# tanaBoard.net
KiCad netlist of a schematic drawn in EasyEDA
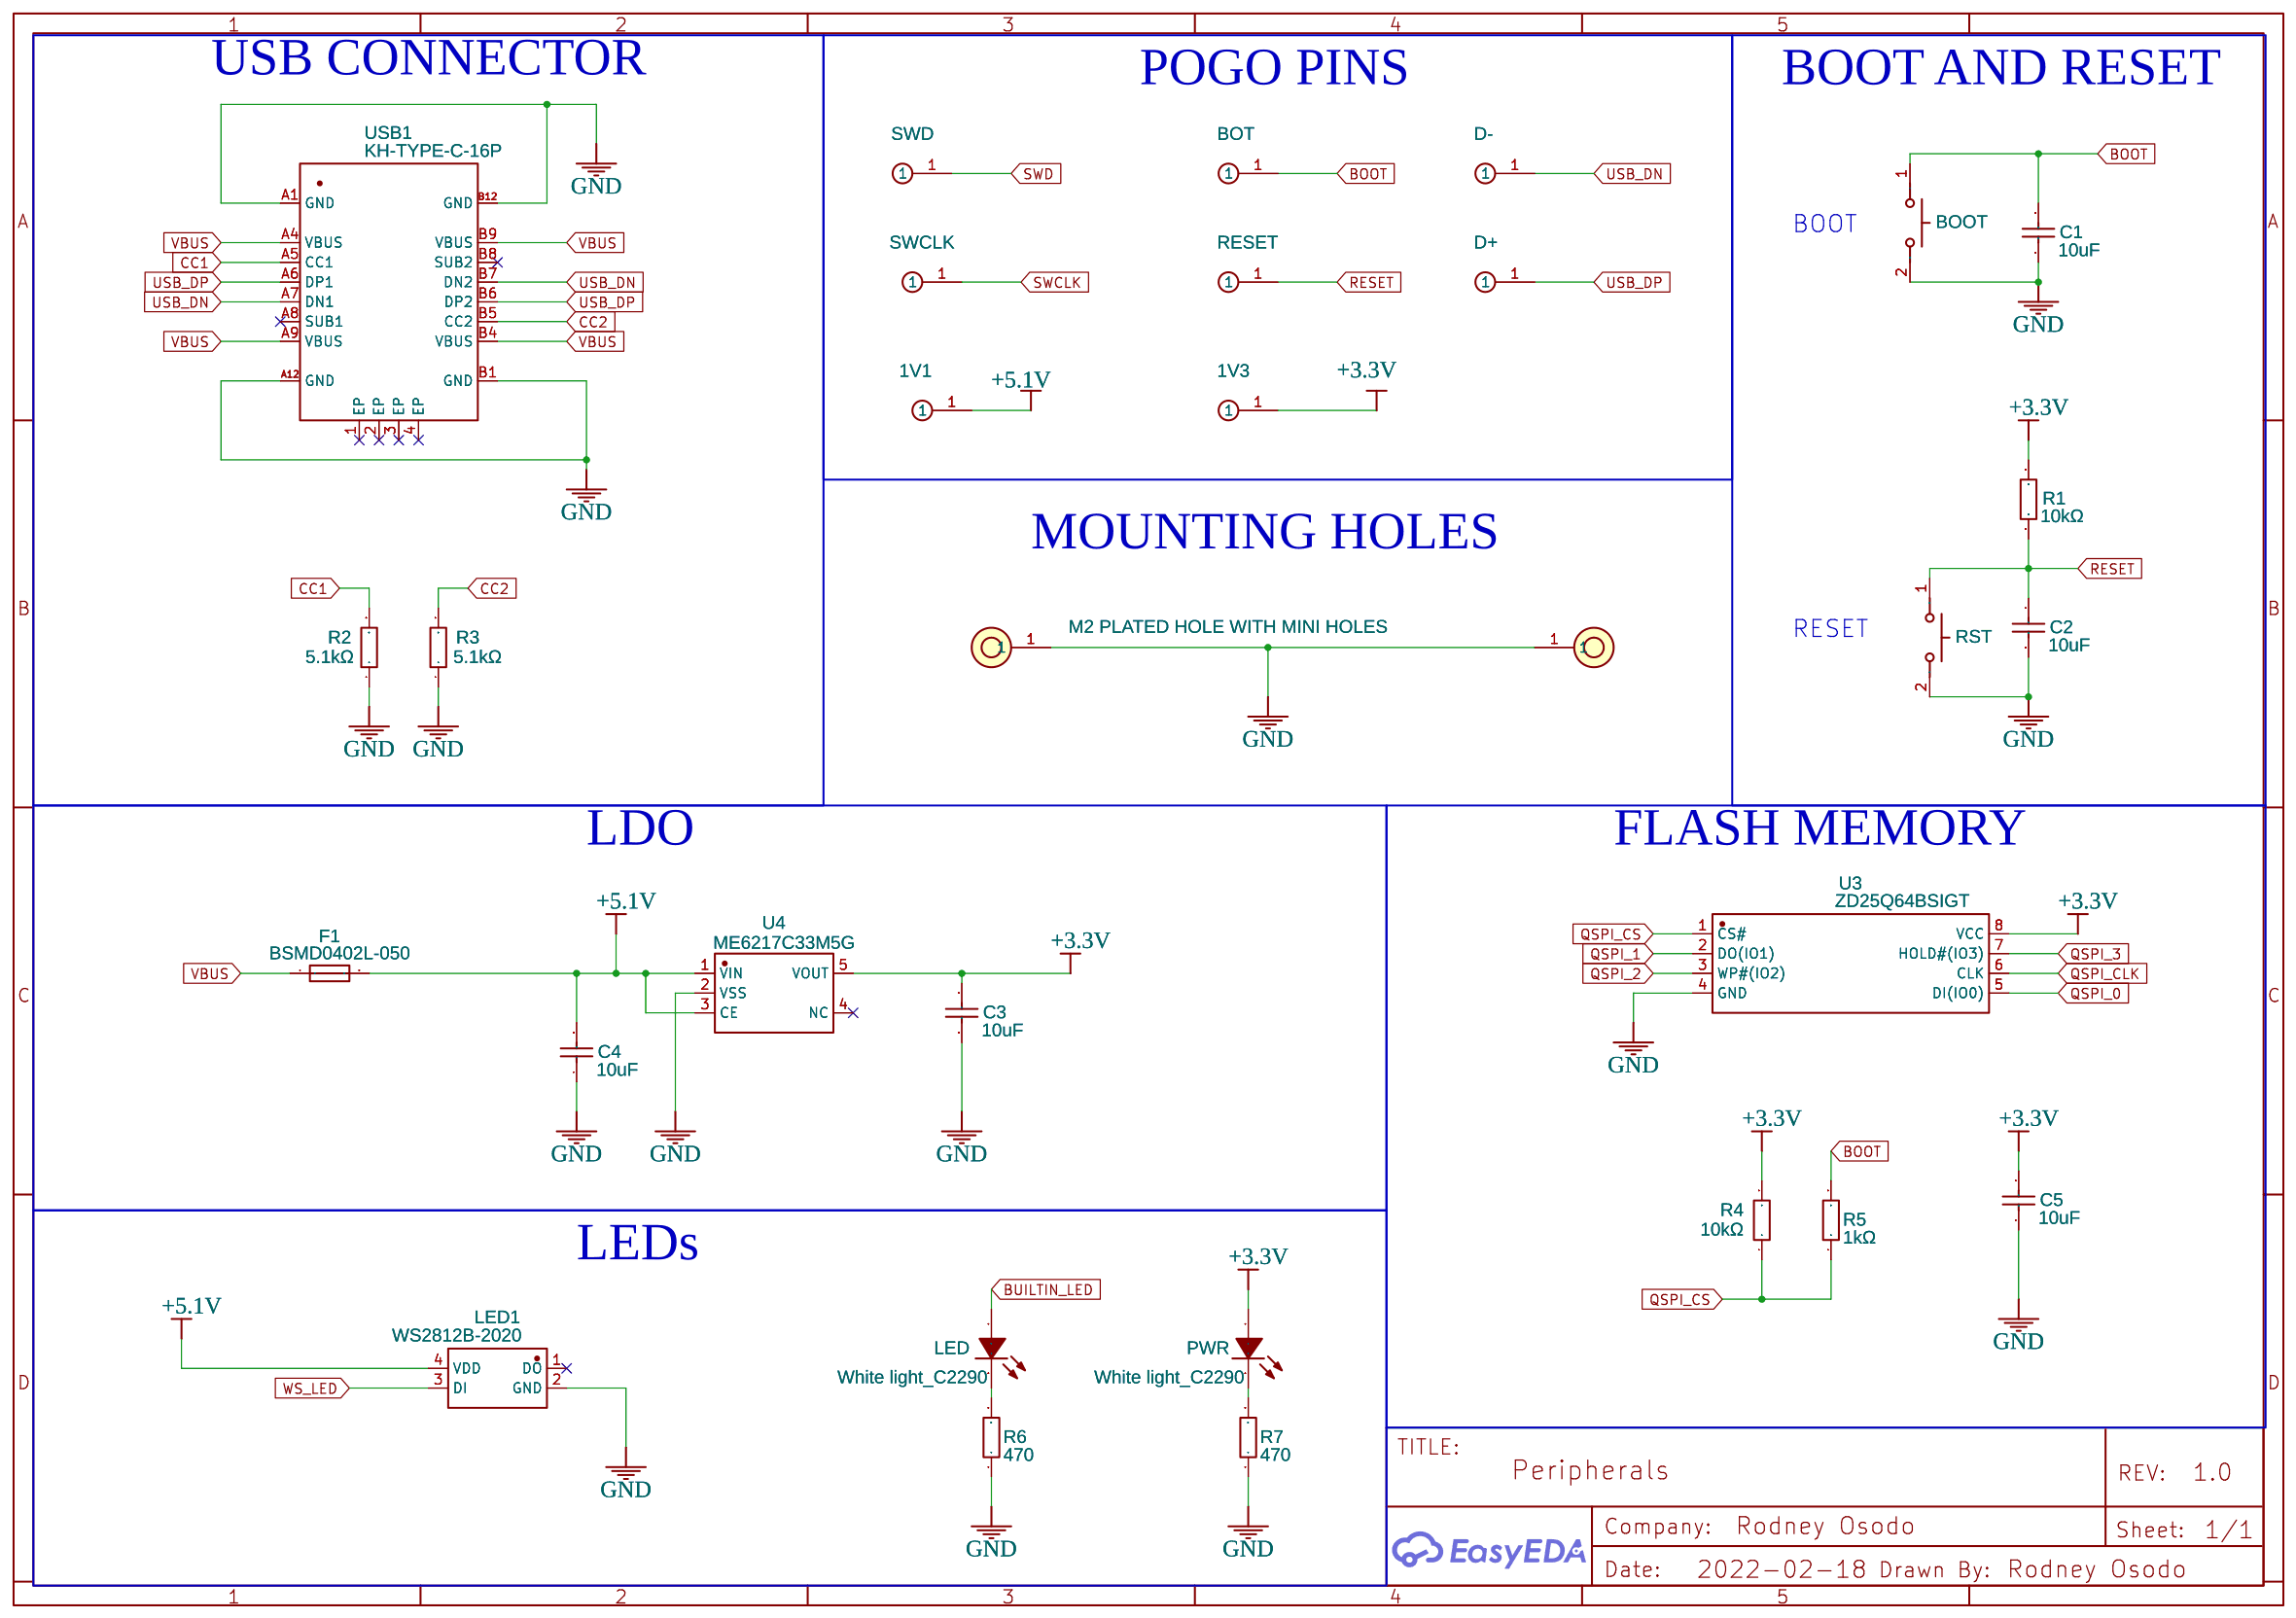
[diagram p0: Peripherals]
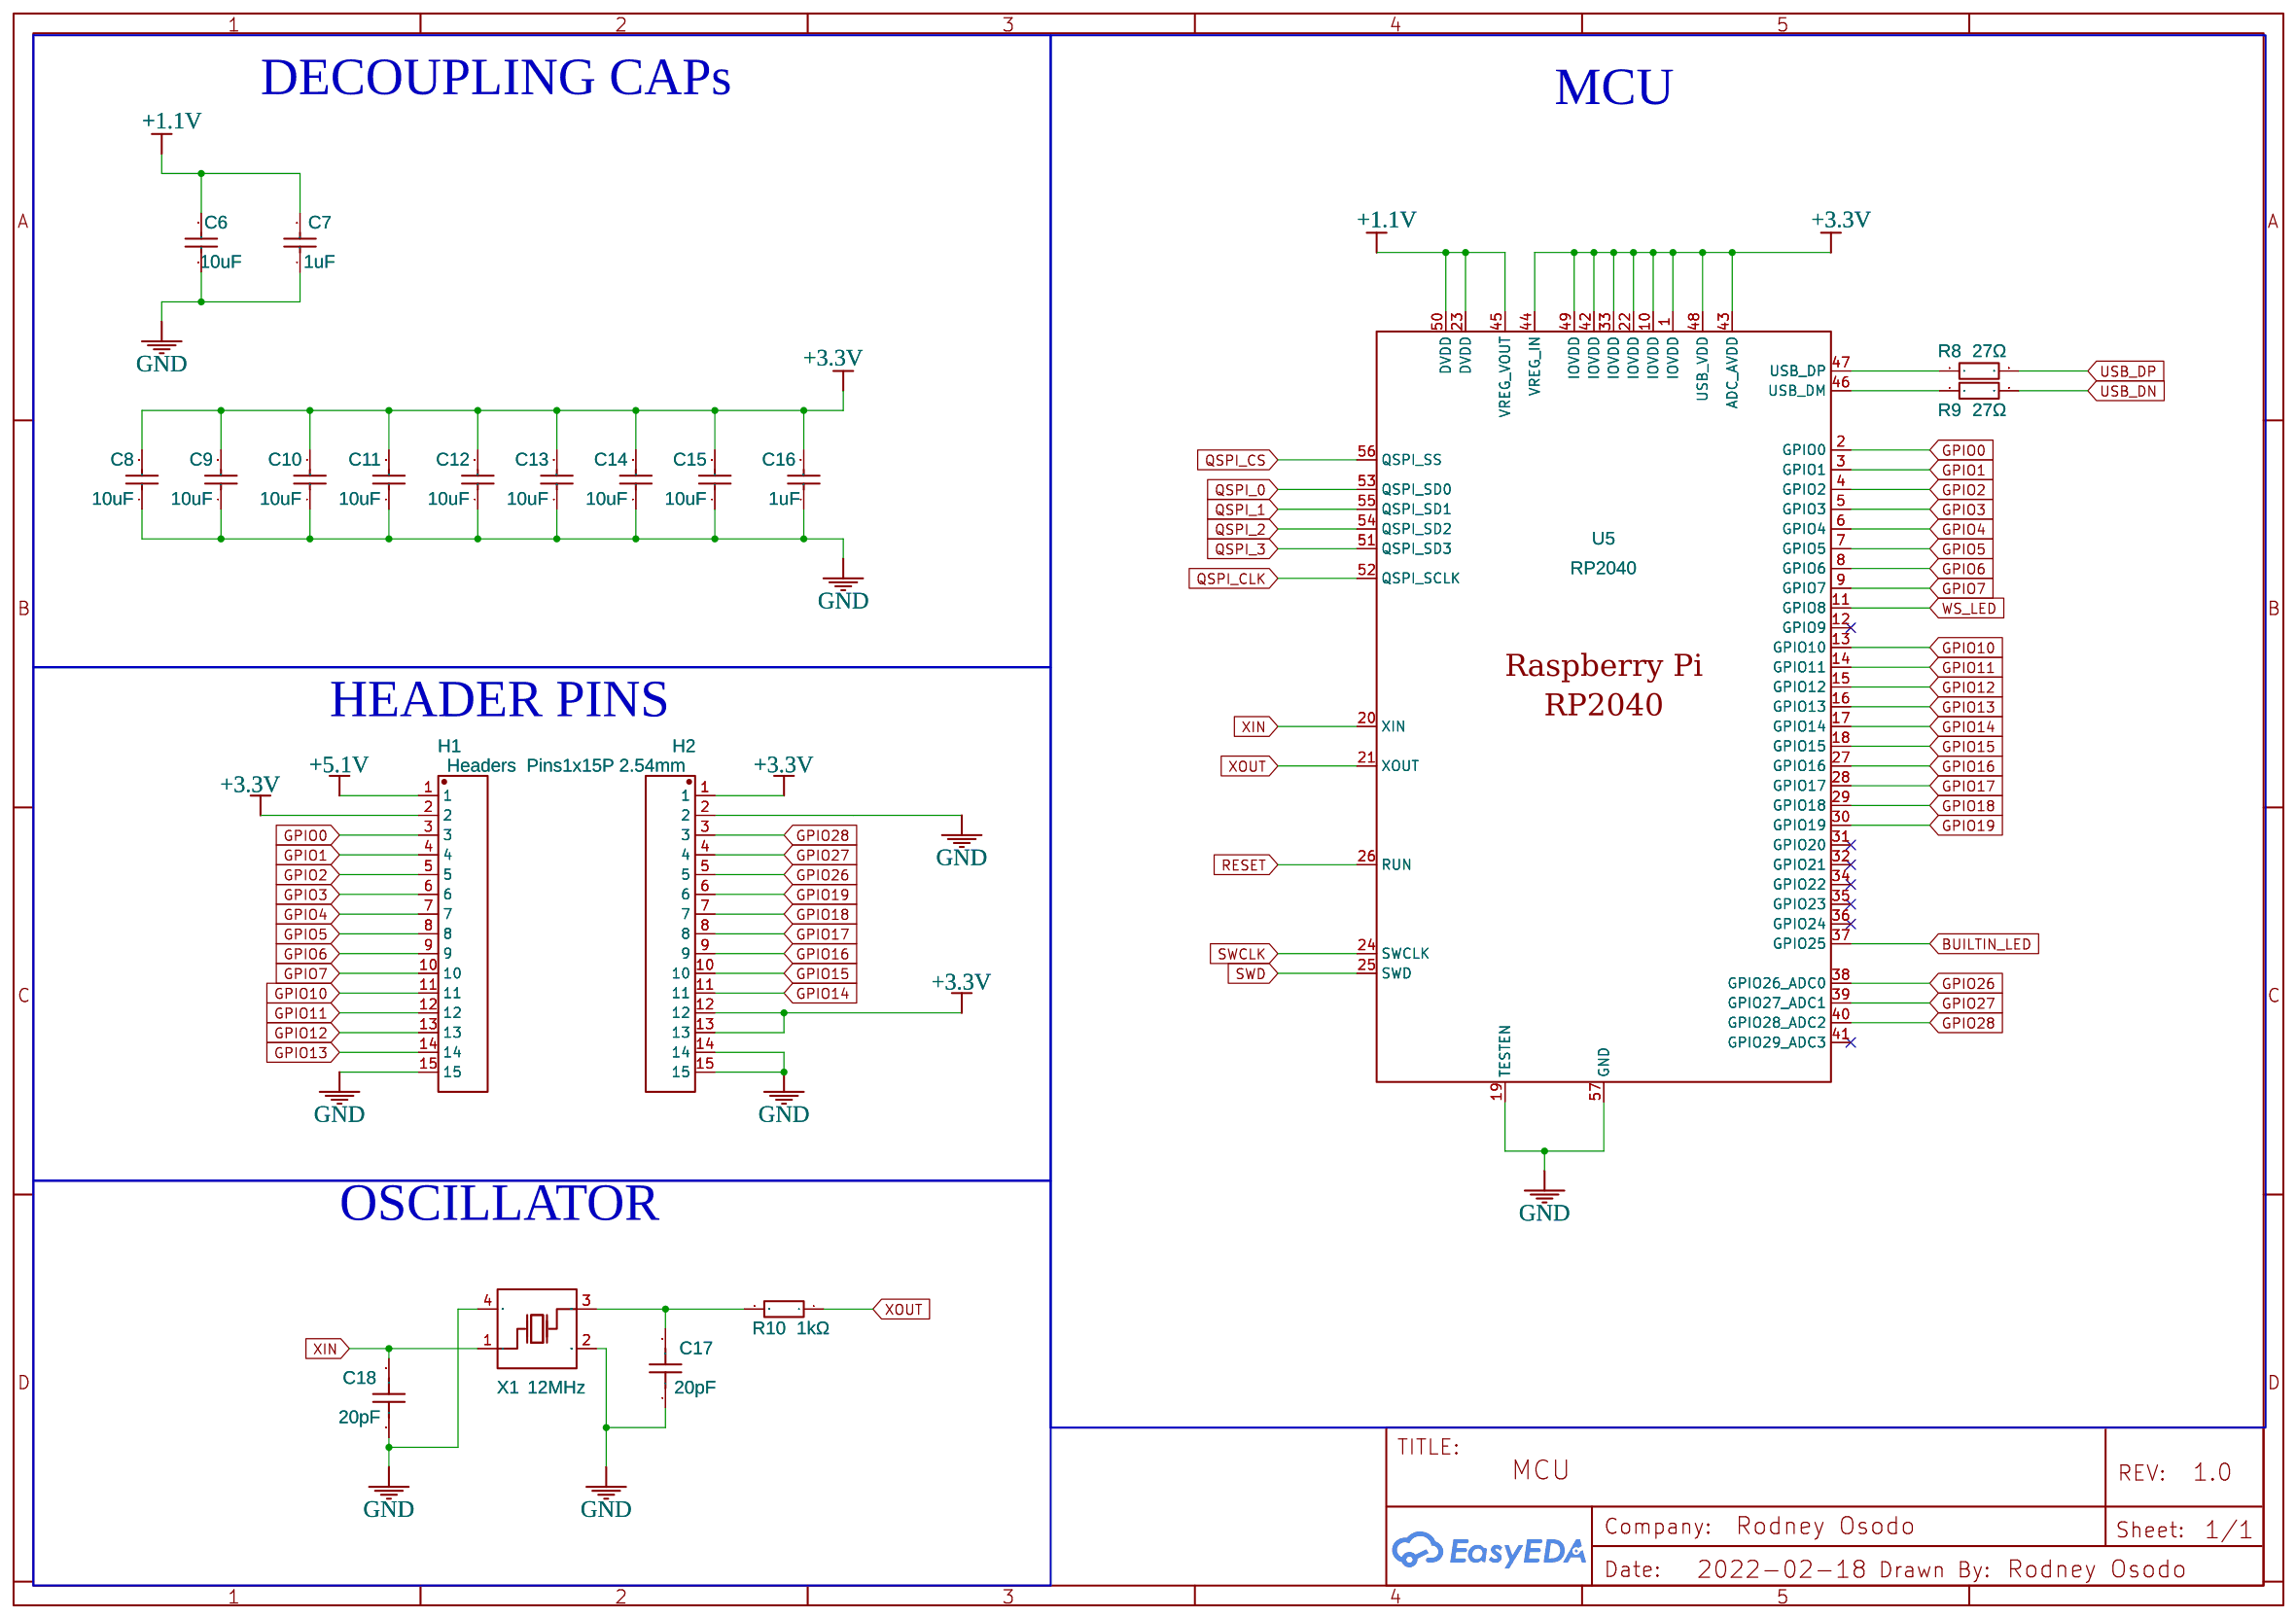
[diagram p1: MCU]

(export (version "E")
  (design (tool "Eeschema 10.0.6"))
  (components
    (comp (ref "1V1") (value "testpoint") (libsource (lib "") (part "testpoint_1")))
    (comp (ref "1V3") (value "testpoint") (libsource (lib "") (part "testpoint_1")))
    (comp (ref "BOOT")
      (value "SKRKAEE020")
      (fields (field (name "BOM_Supplier Part") "C115357"))
      (libsource (lib "") (part "SKRKAEE020"))
    )
    (comp (ref "BOT") (value "testpoint") (libsource (lib "") (part "testpoint")))
    (comp (ref "C1")
      (value "10uF")
      (fields
        (field (name "BOM_Manufacturer Part") "CL05A106MQ5NUNC")
        (field (name "BOM_Supplier Part") "C15525")
      )
      (libsource (lib "") (part "CL05A106MQ5NUNC_1"))
    )
    (comp (ref "C2")
      (value "10uF")
      (fields
        (field (name "BOM_Manufacturer Part") "CL05A106MQ5NUNC")
        (field (name "BOM_Supplier Part") "C15525")
      )
      (libsource (lib "") (part "CL05A106MQ5NUNC_1"))
    )
    (comp (ref "C3")
      (value "10uF")
      (fields
        (field (name "BOM_Manufacturer Part") "CL05A106MQ5NUNC")
        (field (name "BOM_Supplier Part") "C15525")
      )
      (libsource (lib "") (part "CL05A106MQ5NUNC"))
    )
    (comp (ref "C4")
      (value "10uF")
      (fields
        (field (name "BOM_Manufacturer Part") "CL05A106MQ5NUNC")
        (field (name "BOM_Supplier Part") "C15525")
      )
      (libsource (lib "") (part "CL05A106MQ5NUNC"))
    )
    (comp (ref "C5")
      (value "10uF")
      (fields
        (field (name "BOM_Manufacturer Part") "CL05A106MQ5NUNC")
        (field (name "BOM_Supplier Part") "C15525")
      )
      (libsource (lib "") (part "CL05A106MQ5NUNC"))
    )
    (comp (ref "D+") (value "testpoint") (libsource (lib "") (part "testpoint_5")))
    (comp (ref "D-") (value "testpoint") (libsource (lib "") (part "testpoint_6")))
    (comp (ref "F1")
      (value "BSMD0402L-050")
      (fields (field (name "BOM_Supplier Part") "C914087"))
      (libsource (lib "") (part "BSMD0402L-050"))
    )
    (comp (ref "LED")
      (value "White light_C2290")
      (fields
        (field (name "BOM_Manufacturer Part") "0603White light")
        (field (name "BOM_Supplier Part") "C2290")
      )
      (libsource (lib "") (part "0603White light_C2290"))
    )
    (comp (ref "LED1")
      (value "WS2812B-2020")
      (fields (field (name "BOM_Supplier Part") "C965555"))
      (libsource (lib "") (part "WS2812B-2020"))
    )
    (comp (ref "PWR")
      (value "White light_C2290")
      (fields
        (field (name "BOM_Manufacturer Part") "0603White light")
        (field (name "BOM_Supplier Part") "C2290")
      )
      (libsource (lib "") (part "0603White light_C2290_1"))
    )
    (comp (ref "R1")
      (value "10kΩ")
      (fields
        (field (name "BOM_Manufacturer Part") "RC-02W1002FT")
        (field (name "BOM_Supplier Part") "C258091")
      )
      (libsource (lib "") (part "RC-02W1002FT"))
    )
    (comp (ref "R2")
      (value "5.1kΩ")
      (fields
        (field (name "BOM_Manufacturer Part") "RC-02W5101FT")
        (field (name "BOM_Supplier Part") "C294638")
      )
      (libsource (lib "") (part "RC-02W5101FT"))
    )
    (comp (ref "R3")
      (value "5.1kΩ")
      (fields
        (field (name "BOM_Manufacturer Part") "RC-02W5101FT")
        (field (name "BOM_Supplier Part") "C294638")
      )
      (libsource (lib "") (part "RC-02W5101FT"))
    )
    (comp (ref "R4")
      (value "10kΩ")
      (fields
        (field (name "BOM_Manufacturer Part") "RC-02W1002FT")
        (field (name "BOM_Supplier Part") "C258091")
      )
      (libsource (lib "") (part "RC-02W1002FT"))
    )
    (comp (ref "R5")
      (value "1kΩ")
      (fields
        (field (name "BOM_Manufacturer Part") "RC-02W1001FT")
        (field (name "BOM_Supplier Part") "C226166")
      )
      (libsource (lib "") (part "RC-02W1001FT"))
    )
    (comp (ref "R6")
      (value "470")
      (fields
        (field (name "BOM_Manufacturer Part") "RC0402FR-07470RL")
        (field (name "BOM_Supplier Part") "C114877")
      )
      (libsource (lib "") (part "RC0402FR-07470RL"))
    )
    (comp (ref "R7")
      (value "470")
      (fields
        (field (name "BOM_Manufacturer Part") "RC0402FR-07470RL")
        (field (name "BOM_Supplier Part") "C114877")
      )
      (libsource (lib "") (part "RC0402FR-07470RL"))
    )
    (comp (ref "RESET") (value "testpoint") (libsource (lib "") (part "testpoint_3")))
    (comp (ref "RST")
      (value "SKRKAEE020")
      (fields (field (name "BOM_Supplier Part") "C115357"))
      (libsource (lib "") (part "SKRKAEE020_1"))
    )
    (comp (ref "SWCLK") (value "testpoint") (libsource (lib "") (part "testpoint_2")))
    (comp (ref "SWD") (value "testpoint") (libsource (lib "") (part "testpoint_4")))
    (comp (ref "U1")
      (value "M2 PLATED HOLE WITH MINI HOLES")
      (libsource (lib "") (part "M2 PLATED HOLE WITH MINI HOLES_1"))
    )
    (comp (ref "U2")
      (value "M2 PLATED HOLE WITH MINI HOLES")
      (libsource (lib "") (part "M2 PLATED HOLE WITH MINI HOLES"))
    )
    (comp (ref "U3")
      (value "ZD25Q64BSIGT")
      (fields (field (name "BOM_Supplier Part") "C2687407"))
      (libsource (lib "") (part "ZD25Q64BSIGT"))
    )
    (comp (ref "U4")
      (value "ME6217C33M5G")
      (fields (field (name "BOM_Supplier Part") "C427602"))
      (libsource (lib "") (part "ME6217C33M5G"))
    )
    (comp (ref "USB1")
      (value "KH-TYPE-C-16P")
      (fields (field (name "BOM_Supplier Part") "C709357"))
      (libsource (lib "") (part "KH-TYPE-C-16P"))
    )
    (comp (ref "C6")
      (value "10uF")
      (fields
        (field (name "BOM_Manufacturer Part") "CL05A106MQ5NUNC")
        (field (name "BOM_Supplier Part") "C15525")
      )
      (libsource (lib "") (part "CL05A106MQ5NUNC_1"))
    )
    (comp (ref "C7")
      (value "1uF")
      (fields
        (field (name "BOM_Manufacturer Part") "CL05A105KP5NNNC")
        (field (name "BOM_Supplier Part") "C14445")
      )
      (libsource (lib "") (part "CL05A105KP5NNNC"))
    )
    (comp (ref "C8")
      (value "10uF")
      (fields
        (field (name "BOM_Manufacturer Part") "CL05A106MQ5NUNC")
        (field (name "BOM_Supplier Part") "C15525")
      )
      (libsource (lib "") (part "CL05A106MQ5NUNC"))
    )
    (comp (ref "C9")
      (value "10uF")
      (fields
        (field (name "BOM_Manufacturer Part") "CL05A106MQ5NUNC")
        (field (name "BOM_Supplier Part") "C15525")
      )
      (libsource (lib "") (part "CL05A106MQ5NUNC"))
    )
    (comp (ref "C10")
      (value "10uF")
      (fields
        (field (name "BOM_Manufacturer Part") "CL05A106MQ5NUNC")
        (field (name "BOM_Supplier Part") "C15525")
      )
      (libsource (lib "") (part "CL05A106MQ5NUNC"))
    )
    (comp (ref "C11")
      (value "10uF")
      (fields
        (field (name "BOM_Manufacturer Part") "CL05A106MQ5NUNC")
        (field (name "BOM_Supplier Part") "C15525")
      )
      (libsource (lib "") (part "CL05A106MQ5NUNC"))
    )
    (comp (ref "C12")
      (value "10uF")
      (fields
        (field (name "BOM_Manufacturer Part") "CL05A106MQ5NUNC")
        (field (name "BOM_Supplier Part") "C15525")
      )
      (libsource (lib "") (part "CL05A106MQ5NUNC"))
    )
    (comp (ref "C13")
      (value "10uF")
      (fields
        (field (name "BOM_Manufacturer Part") "CL05A106MQ5NUNC")
        (field (name "BOM_Supplier Part") "C15525")
      )
      (libsource (lib "") (part "CL05A106MQ5NUNC"))
    )
    (comp (ref "C14")
      (value "10uF")
      (fields
        (field (name "BOM_Manufacturer Part") "CL05A106MQ5NUNC")
        (field (name "BOM_Supplier Part") "C15525")
      )
      (libsource (lib "") (part "CL05A106MQ5NUNC"))
    )
    (comp (ref "C15")
      (value "10uF")
      (fields
        (field (name "BOM_Manufacturer Part") "CL05A106MQ5NUNC")
        (field (name "BOM_Supplier Part") "C15525")
      )
      (libsource (lib "") (part "CL05A106MQ5NUNC"))
    )
    (comp (ref "C16")
      (value "1uF")
      (fields
        (field (name "BOM_Manufacturer Part") "CL05A105KP5NNNC")
        (field (name "BOM_Supplier Part") "C14445")
      )
      (libsource (lib "") (part "CL05A105KP5NNNC_1"))
    )
    (comp (ref "C17")
      (value "20pF")
      (fields
        (field (name "BOM_Manufacturer Part") "0402CG200F500NT")
        (field (name "BOM_Supplier Part") "C182483")
      )
      (libsource (lib "") (part "0402CG200F500NT"))
    )
    (comp (ref "C18")
      (value "20pF")
      (fields
        (field (name "BOM_Manufacturer Part") "0402CG200F500NT")
        (field (name "BOM_Supplier Part") "C182483")
      )
      (libsource (lib "") (part "0402CG200F500NT"))
    )
    (comp (ref "H1")
      (value "Headers  Pins1x15P 2.54mm")
      (fields (field (name "BOM_Supplier Part") "C54102"))
      (libsource (lib "") (part "Headers  Pins1x15P 2.54mm"))
    )
    (comp (ref "H2")
      (value "Headers  Pins1x15P 2.54mm")
      (fields (field (name "BOM_Supplier Part") "C54102"))
      (libsource (lib "") (part "Headers  Pins1x15P 2.54mm_1"))
    )
    (comp (ref "R8")
      (value "27Ω")
      (fields
        (field (name "BOM_Manufacturer Part") "RC-02W27R0FT")
        (field (name "BOM_Supplier Part") "C321419")
      )
      (libsource (lib "") (part "RC-02W27R0FT"))
    )
    (comp (ref "R9")
      (value "27Ω")
      (fields
        (field (name "BOM_Manufacturer Part") "RC-02W27R0FT")
        (field (name "BOM_Supplier Part") "C321419")
      )
      (libsource (lib "") (part "RC-02W27R0FT"))
    )
    (comp (ref "R10")
      (value "1kΩ")
      (fields
        (field (name "BOM_Manufacturer Part") "RC-02W1001FT")
        (field (name "BOM_Supplier Part") "C226166")
      )
      (libsource (lib "") (part "RC-02W1001FT"))
    )
    (comp (ref "U5")
      (value "RP2040")
      (fields (field (name "BOM_Supplier Part") "C2040"))
      (libsource (lib "") (part "RP2040"))
    )
    (comp (ref "X1")
      (value "12MHz")
      (fields
        (field (name "BOM_Manufacturer Part") "X322512MSB4SI")
        (field (name "BOM_Supplier Part") "C9002")
      )
      (libsource (lib "") (part "X322512MSB4SI"))
    )
  )
  (nets
    (net (code "1") (name "+1.1V") (class "Default")
      (node (ref "C6") (pin "2") (pinfunction "2_2") (pintype "input"))
      (node (ref "C7") (pin "2") (pinfunction "2_2") (pintype "input"))
      (node (ref "U5") (pin "23") (pinfunction "DVDD_23") (pintype "bidirectional"))
      (node (ref "U5") (pin "45") (pinfunction "VREG_VOUT_45") (pintype "bidirectional"))
      (node (ref "U5") (pin "50") (pinfunction "DVDD_50") (pintype "bidirectional"))
    )
    (net (code "2") (name "+3.3V") (class "Default")
      (node (ref "1V3") (pin "1") (pinfunction "1_1") (pintype "unspecified"))
      (node (ref "C10") (pin "2") (pinfunction "2_2") (pintype "input"))
      (node (ref "C11") (pin "2") (pinfunction "2_2") (pintype "input"))
      (node (ref "C12") (pin "2") (pinfunction "2_2") (pintype "input"))
      (node (ref "C13") (pin "2") (pinfunction "2_2") (pintype "input"))
      (node (ref "C14") (pin "2") (pinfunction "2_2") (pintype "input"))
      (node (ref "C15") (pin "2") (pinfunction "2_2") (pintype "input"))
      (node (ref "C16") (pin "2") (pinfunction "2_2") (pintype "input"))
      (node (ref "C3") (pin "2") (pinfunction "2_2") (pintype "input"))
      (node (ref "C5") (pin "2") (pinfunction "2_2") (pintype "input"))
      (node (ref "C8") (pin "2") (pinfunction "2_2") (pintype "input"))
      (node (ref "C9") (pin "2") (pinfunction "2_2") (pintype "input"))
      (node (ref "H1") (pin "2") (pinfunction "2_2") (pintype "unspecified"))
      (node (ref "H2") (pin "1") (pinfunction "1_1") (pintype "unspecified"))
      (node (ref "H2") (pin "12") (pinfunction "12_12") (pintype "unspecified"))
      (node (ref "H2") (pin "13") (pinfunction "13_13") (pintype "unspecified"))
      (node (ref "PWR") (pin "1") (pinfunction "A_1") (pintype "unspecified"))
      (node (ref "R1") (pin "2") (pinfunction "2_2") (pintype "unspecified"))
      (node (ref "R4") (pin "2") (pinfunction "2_2") (pintype "unspecified"))
      (node (ref "U3") (pin "8") (pinfunction "VCC_8") (pintype "unspecified"))
      (node (ref "U4") (pin "5") (pinfunction "VOUT_5") (pintype "unspecified"))
      (node (ref "U5") (pin "1") (pinfunction "IOVDD_1") (pintype "bidirectional"))
      (node (ref "U5") (pin "10") (pinfunction "IOVDD_10") (pintype "bidirectional"))
      (node (ref "U5") (pin "22") (pinfunction "IOVDD_22") (pintype "bidirectional"))
      (node (ref "U5") (pin "33") (pinfunction "IOVDD_33") (pintype "bidirectional"))
      (node (ref "U5") (pin "42") (pinfunction "IOVDD_42") (pintype "bidirectional"))
      (node (ref "U5") (pin "43") (pinfunction "ADC_AVDD_43") (pintype "bidirectional"))
      (node (ref "U5") (pin "44") (pinfunction "VREG_IN_44") (pintype "bidirectional"))
      (node (ref "U5") (pin "48") (pinfunction "USB_VDD_48") (pintype "bidirectional"))
      (node (ref "U5") (pin "49") (pinfunction "IOVDD_49") (pintype "bidirectional"))
    )
    (net (code "3") (name "+5.1V") (class "Default")
      (node (ref "1V1") (pin "1") (pinfunction "1_1") (pintype "unspecified"))
      (node (ref "C4") (pin "2") (pinfunction "2_2") (pintype "input"))
      (node (ref "F1") (pin "2") (pinfunction "2_2") (pintype "unspecified"))
      (node (ref "H1") (pin "1") (pinfunction "1_1") (pintype "unspecified"))
      (node (ref "LED1") (pin "4") (pinfunction "VDD_4") (pintype "unspecified"))
      (node (ref "U4") (pin "1") (pinfunction "VIN_1") (pintype "unspecified"))
      (node (ref "U4") (pin "3") (pinfunction "CE_3") (pintype "unspecified"))
    )
    (net (code "4") (name "BOOT") (class "Default")
      (node (ref "BOOT") (pin "1") (pinfunction "1_1") (pintype "unspecified"))
      (node (ref "BOT") (pin "1") (pinfunction "1_1") (pintype "unspecified"))
      (node (ref "C1") (pin "1") (pinfunction "1_1") (pintype "input"))
      (node (ref "R5") (pin "2") (pinfunction "2_2") (pintype "unspecified"))
    )
    (net (code "5") (name "BUILTIN_LED") (class "Default")
      (node (ref "LED") (pin "1") (pinfunction "A_1") (pintype "unspecified"))
      (node (ref "U5") (pin "37") (pinfunction "GPIO25_37") (pintype "bidirectional"))
    )
    (net (code "6") (name "CC1") (class "Default")
      (node (ref "R2") (pin "2") (pinfunction "2_2") (pintype "unspecified"))
      (node (ref "USB1") (pin "A5") (pinfunction "CC1_A5") (pintype "unspecified"))
    )
    (net (code "7") (name "CC2") (class "Default")
      (node (ref "R3") (pin "2") (pinfunction "2_2") (pintype "unspecified"))
      (node (ref "USB1") (pin "B5") (pinfunction "CC2_B5") (pintype "unspecified"))
    )
    (net (code "8") (name "GND") (class "Default")
      (node (ref "BOOT") (pin "2") (pinfunction "2_2") (pintype "unspecified"))
      (node (ref "C1") (pin "2") (pinfunction "2_2") (pintype "input"))
      (node (ref "C10") (pin "1") (pinfunction "1_1") (pintype "input"))
      (node (ref "C11") (pin "1") (pinfunction "1_1") (pintype "input"))
      (node (ref "C12") (pin "1") (pinfunction "1_1") (pintype "input"))
      (node (ref "C13") (pin "1") (pinfunction "1_1") (pintype "input"))
      (node (ref "C14") (pin "1") (pinfunction "1_1") (pintype "input"))
      (node (ref "C15") (pin "1") (pinfunction "1_1") (pintype "input"))
      (node (ref "C16") (pin "1") (pinfunction "1_1") (pintype "input"))
      (node (ref "C17") (pin "1") (pinfunction "1_1") (pintype "unspecified"))
      (node (ref "C18") (pin "1") (pinfunction "1_1") (pintype "unspecified"))
      (node (ref "C2") (pin "2") (pinfunction "2_2") (pintype "input"))
      (node (ref "C3") (pin "1") (pinfunction "1_1") (pintype "input"))
      (node (ref "C4") (pin "1") (pinfunction "1_1") (pintype "input"))
      (node (ref "C5") (pin "1") (pinfunction "1_1") (pintype "input"))
      (node (ref "C6") (pin "1") (pinfunction "1_1") (pintype "input"))
      (node (ref "C7") (pin "1") (pinfunction "1_1") (pintype "input"))
      (node (ref "C8") (pin "1") (pinfunction "1_1") (pintype "input"))
      (node (ref "C9") (pin "1") (pinfunction "1_1") (pintype "input"))
      (node (ref "H1") (pin "15") (pinfunction "15_15") (pintype "unspecified"))
      (node (ref "H2") (pin "14") (pinfunction "14_14") (pintype "unspecified"))
      (node (ref "H2") (pin "15") (pinfunction "15_15") (pintype "unspecified"))
      (node (ref "H2") (pin "2") (pinfunction "2_2") (pintype "unspecified"))
      (node (ref "LED1") (pin "2") (pinfunction "GND_2") (pintype "unspecified"))
      (node (ref "R2") (pin "1") (pinfunction "1_1") (pintype "unspecified"))
      (node (ref "R3") (pin "1") (pinfunction "1_1") (pintype "unspecified"))
      (node (ref "R6") (pin "1") (pinfunction "1_1") (pintype "input"))
      (node (ref "R7") (pin "1") (pinfunction "1_1") (pintype "input"))
      (node (ref "RST") (pin "2") (pinfunction "2_2") (pintype "unspecified"))
      (node (ref "U1") (pin "1") (pinfunction "1_1") (pintype "unspecified"))
      (node (ref "U2") (pin "1") (pinfunction "1_1") (pintype "unspecified"))
      (node (ref "U3") (pin "4") (pinfunction "GND_4") (pintype "unspecified"))
      (node (ref "U4") (pin "2") (pinfunction "VSS_2") (pintype "unspecified"))
      (node (ref "U5") (pin "19") (pinfunction "TESTEN_19") (pintype "unspecified"))
      (node (ref "U5") (pin "57") (pinfunction "GND_57") (pintype "bidirectional"))
      (node (ref "USB1") (pin "A1") (pinfunction "GND_A1") (pintype "unspecified"))
      (node (ref "USB1") (pin "A12") (pinfunction "GND_A12") (pintype "unspecified"))
      (node (ref "USB1") (pin "B1") (pinfunction "GND_B1") (pintype "unspecified"))
      (node (ref "USB1") (pin "B12") (pinfunction "GND_B12") (pintype "unspecified"))
      (node (ref "X1") (pin "2") (pinfunction "GND_2") (pintype "unspecified"))
      (node (ref "X1") (pin "4") (pinfunction "GND_4") (pintype "unspecified"))
    )
    (net (code "9") (name "GPIO0") (class "Default")
      (node (ref "H1") (pin "3") (pinfunction "3_3") (pintype "unspecified"))
      (node (ref "U5") (pin "2") (pinfunction "GPIO0_2") (pintype "bidirectional"))
    )
    (net (code "10") (name "GPIO1") (class "Default")
      (node (ref "H1") (pin "4") (pinfunction "4_4") (pintype "unspecified"))
      (node (ref "U5") (pin "3") (pinfunction "GPIO1_3") (pintype "bidirectional"))
    )
    (net (code "11") (name "GPIO2") (class "Default")
      (node (ref "H1") (pin "5") (pinfunction "5_5") (pintype "unspecified"))
      (node (ref "U5") (pin "4") (pinfunction "GPIO2_4") (pintype "bidirectional"))
    )
    (net (code "12") (name "GPIO3") (class "Default")
      (node (ref "H1") (pin "6") (pinfunction "6_6") (pintype "unspecified"))
      (node (ref "U5") (pin "5") (pinfunction "GPIO3_5") (pintype "bidirectional"))
    )
    (net (code "13") (name "GPIO4") (class "Default")
      (node (ref "H1") (pin "7") (pinfunction "7_7") (pintype "unspecified"))
      (node (ref "U5") (pin "6") (pinfunction "GPIO4_6") (pintype "bidirectional"))
    )
    (net (code "14") (name "GPIO5") (class "Default")
      (node (ref "H1") (pin "8") (pinfunction "8_8") (pintype "unspecified"))
      (node (ref "U5") (pin "7") (pinfunction "GPIO5_7") (pintype "bidirectional"))
    )
    (net (code "15") (name "GPIO6") (class "Default")
      (node (ref "H1") (pin "9") (pinfunction "9_9") (pintype "unspecified"))
      (node (ref "U5") (pin "8") (pinfunction "GPIO6_8") (pintype "bidirectional"))
    )
    (net (code "16") (name "GPIO7") (class "Default")
      (node (ref "H1") (pin "10") (pinfunction "10_10") (pintype "unspecified"))
      (node (ref "U5") (pin "9") (pinfunction "GPIO7_9") (pintype "bidirectional"))
    )
    (net (code "17") (name "GPIO10") (class "Default")
      (node (ref "H1") (pin "11") (pinfunction "11_11") (pintype "unspecified"))
      (node (ref "U5") (pin "13") (pinfunction "GPIO10_13") (pintype "bidirectional"))
    )
    (net (code "18") (name "GPIO11") (class "Default")
      (node (ref "H1") (pin "12") (pinfunction "12_12") (pintype "unspecified"))
      (node (ref "U5") (pin "14") (pinfunction "GPIO11_14") (pintype "bidirectional"))
    )
    (net (code "19") (name "GPIO12") (class "Default")
      (node (ref "H1") (pin "13") (pinfunction "13_13") (pintype "unspecified"))
      (node (ref "U5") (pin "15") (pinfunction "GPIO12_15") (pintype "bidirectional"))
    )
    (net (code "20") (name "GPIO13") (class "Default")
      (node (ref "H1") (pin "14") (pinfunction "14_14") (pintype "unspecified"))
      (node (ref "U5") (pin "16") (pinfunction "GPIO13_16") (pintype "bidirectional"))
    )
    (net (code "21") (name "GPIO14") (class "Default")
      (node (ref "H2") (pin "11") (pinfunction "11_11") (pintype "unspecified"))
      (node (ref "U5") (pin "17") (pinfunction "GPIO14_17") (pintype "bidirectional"))
    )
    (net (code "22") (name "GPIO15") (class "Default")
      (node (ref "H2") (pin "10") (pinfunction "10_10") (pintype "unspecified"))
      (node (ref "U5") (pin "18") (pinfunction "GPIO15_18") (pintype "bidirectional"))
    )
    (net (code "23") (name "GPIO16") (class "Default")
      (node (ref "H2") (pin "9") (pinfunction "9_9") (pintype "unspecified"))
      (node (ref "U5") (pin "27") (pinfunction "GPIO16_27") (pintype "bidirectional"))
    )
    (net (code "24") (name "GPIO17") (class "Default")
      (node (ref "H2") (pin "8") (pinfunction "8_8") (pintype "unspecified"))
      (node (ref "U5") (pin "28") (pinfunction "GPIO17_28") (pintype "bidirectional"))
    )
    (net (code "25") (name "GPIO18") (class "Default")
      (node (ref "H2") (pin "7") (pinfunction "7_7") (pintype "unspecified"))
      (node (ref "U5") (pin "29") (pinfunction "GPIO18_29") (pintype "bidirectional"))
    )
    (net (code "26") (name "GPIO19") (class "Default")
      (node (ref "H2") (pin "6") (pinfunction "6_6") (pintype "unspecified"))
      (node (ref "U5") (pin "30") (pinfunction "GPIO19_30") (pintype "bidirectional"))
    )
    (net (code "27") (name "GPIO26") (class "Default")
      (node (ref "H2") (pin "5") (pinfunction "5_5") (pintype "unspecified"))
      (node (ref "U5") (pin "38") (pinfunction "GPIO26_ADC0_38") (pintype "bidirectional"))
    )
    (net (code "28") (name "GPIO27") (class "Default")
      (node (ref "H2") (pin "4") (pinfunction "4_4") (pintype "unspecified"))
      (node (ref "U5") (pin "39") (pinfunction "GPIO27_ADC1_39") (pintype "bidirectional"))
    )
    (net (code "29") (name "GPIO28") (class "Default")
      (node (ref "H2") (pin "3") (pinfunction "3_3") (pintype "unspecified"))
      (node (ref "U5") (pin "40") (pinfunction "GPIO28_ADC2_40") (pintype "bidirectional"))
    )
    (net (code "30") (name "Net-(LED-K)") (class "Default")
      (node (ref "LED") (pin "2") (pinfunction "K_2") (pintype "unspecified"))
      (node (ref "R6") (pin "2") (pinfunction "2_2") (pintype "input"))
    )
    (net (code "31") (name "Net-(PWR-K)") (class "Default")
      (node (ref "PWR") (pin "2") (pinfunction "K_2") (pintype "unspecified"))
      (node (ref "R7") (pin "2") (pinfunction "2_2") (pintype "input"))
    )
    (net (code "32") (name "Net-(U5-USB_DM)") (class "Default")
      (node (ref "R9") (pin "1") (pinfunction "1_1") (pintype "unspecified"))
      (node (ref "U5") (pin "46") (pinfunction "USB_DM_46") (pintype "bidirectional"))
    )
    (net (code "33") (name "Net-(U5-USB_DP)") (class "Default")
      (node (ref "R8") (pin "1") (pinfunction "1_1") (pintype "unspecified"))
      (node (ref "U5") (pin "47") (pinfunction "USB_DP_47") (pintype "bidirectional"))
    )
    (net (code "34") (name "Net-(X1-OSC2)") (class "Default")
      (node (ref "C17") (pin "2") (pinfunction "2_2") (pintype "unspecified"))
      (node (ref "R10") (pin "2") (pinfunction "2_2") (pintype "unspecified"))
      (node (ref "X1") (pin "3") (pinfunction "OSC2_3") (pintype "unspecified"))
    )
    (net (code "35") (name "QSPI_0") (class "Default")
      (node (ref "U3") (pin "5") (pinfunction "DI(IO0)_5") (pintype "unspecified"))
      (node (ref "U5") (pin "53") (pinfunction "QSPI_SD0_53") (pintype "bidirectional"))
    )
    (net (code "36") (name "QSPI_1") (class "Default")
      (node (ref "U3") (pin "2") (pinfunction "DO(IO1)_2") (pintype "unspecified"))
      (node (ref "U5") (pin "55") (pinfunction "QSPI_SD1_55") (pintype "bidirectional"))
    )
    (net (code "37") (name "QSPI_2") (class "Default")
      (node (ref "U3") (pin "3") (pinfunction "WP#(IO2)_3") (pintype "unspecified"))
      (node (ref "U5") (pin "54") (pinfunction "QSPI_SD2_54") (pintype "bidirectional"))
    )
    (net (code "38") (name "QSPI_3") (class "Default")
      (node (ref "U3") (pin "7") (pinfunction "HOLD#(IO3)_7") (pintype "unspecified"))
      (node (ref "U5") (pin "51") (pinfunction "QSPI_SD3_51") (pintype "bidirectional"))
    )
    (net (code "39") (name "QSPI_CLK") (class "Default")
      (node (ref "U3") (pin "6") (pinfunction "CLK_6") (pintype "unspecified"))
      (node (ref "U5") (pin "52") (pinfunction "QSPI_SCLK_52") (pintype "output"))
    )
    (net (code "40") (name "QSPI_CS") (class "Default")
      (node (ref "R4") (pin "1") (pinfunction "1_1") (pintype "unspecified"))
      (node (ref "R5") (pin "1") (pinfunction "1_1") (pintype "unspecified"))
      (node (ref "U3") (pin "1") (pinfunction "CS#_1") (pintype "unspecified"))
      (node (ref "U5") (pin "56") (pinfunction "QSPI_SS_56") (pintype "bidirectional"))
    )
    (net (code "41") (name "RESET") (class "Default")
      (node (ref "C2") (pin "1") (pinfunction "1_1") (pintype "input"))
      (node (ref "R1") (pin "1") (pinfunction "1_1") (pintype "unspecified"))
      (node (ref "RESET") (pin "1") (pinfunction "1_1") (pintype "unspecified"))
      (node (ref "RST") (pin "1") (pinfunction "1_1") (pintype "unspecified"))
      (node (ref "U5") (pin "26") (pinfunction "RUN_26") (pintype "input"))
    )
    (net (code "42") (name "SWCLK") (class "Default")
      (node (ref "SWCLK") (pin "1") (pinfunction "1_1") (pintype "unspecified"))
      (node (ref "U5") (pin "24") (pinfunction "SWCLK_24") (pintype "output"))
    )
    (net (code "43") (name "SWD") (class "Default")
      (node (ref "SWD") (pin "1") (pinfunction "1_1") (pintype "unspecified"))
      (node (ref "U5") (pin "25") (pinfunction "SWD_25") (pintype "bidirectional"))
    )
    (net (code "44") (name "USB_DN") (class "Default")
      (node (ref "D-") (pin "1") (pinfunction "1_1") (pintype "unspecified"))
      (node (ref "R9") (pin "2") (pinfunction "2_2") (pintype "unspecified"))
      (node (ref "USB1") (pin "A7") (pinfunction "DN1_A7") (pintype "unspecified"))
      (node (ref "USB1") (pin "B7") (pinfunction "DN2_B7") (pintype "unspecified"))
    )
    (net (code "45") (name "USB_DP") (class "Default")
      (node (ref "D+") (pin "1") (pinfunction "1_1") (pintype "unspecified"))
      (node (ref "R8") (pin "2") (pinfunction "2_2") (pintype "unspecified"))
      (node (ref "USB1") (pin "A6") (pinfunction "DP1_A6") (pintype "unspecified"))
      (node (ref "USB1") (pin "B6") (pinfunction "DP2_B6") (pintype "unspecified"))
    )
    (net (code "46") (name "VBUS") (class "Default")
      (node (ref "F1") (pin "1") (pinfunction "1_1") (pintype "unspecified"))
      (node (ref "USB1") (pin "A4") (pinfunction "VBUS_A4") (pintype "unspecified"))
      (node (ref "USB1") (pin "A9") (pinfunction "VBUS_A9") (pintype "unspecified"))
      (node (ref "USB1") (pin "B4") (pinfunction "VBUS_B4") (pintype "unspecified"))
      (node (ref "USB1") (pin "B9") (pinfunction "VBUS_B9") (pintype "unspecified"))
    )
    (net (code "47") (name "WS_LED") (class "Default")
      (node (ref "LED1") (pin "3") (pinfunction "DI_3") (pintype "unspecified"))
      (node (ref "U5") (pin "11") (pinfunction "GPIO8_11") (pintype "bidirectional"))
    )
    (net (code "48") (name "XIN") (class "Default")
      (node (ref "C18") (pin "2") (pinfunction "2_2") (pintype "unspecified"))
      (node (ref "U5") (pin "20") (pinfunction "XIN_20") (pintype "input"))
      (node (ref "X1") (pin "1") (pinfunction "OSC1_1") (pintype "unspecified"))
    )
    (net (code "49") (name "XOUT") (class "Default")
      (node (ref "R10") (pin "1") (pinfunction "1_1") (pintype "unspecified"))
      (node (ref "U5") (pin "21") (pinfunction "XOUT_21") (pintype "unspecified"))
    )
    (net (code "50") (name "unconnected-(LED1-DO-Pad1)") (class "Default")
      (node (ref "LED1") (pin "1") (pinfunction "DO_1") (pintype "unspecified+no_connect"))
    )
    (net (code "51") (name "unconnected-(U4-NC-Pad4)") (class "Default")
      (node (ref "U4") (pin "4") (pinfunction "NC_4") (pintype "unspecified+no_connect"))
    )
    (net (code "52") (name "unconnected-(U5-GPIO9-Pad12)") (class "Default")
      (node (ref "U5") (pin "12") (pinfunction "GPIO9_12") (pintype "bidirectional+no_connect"))
    )
    (net (code "53") (name "unconnected-(U5-GPIO20-Pad31)") (class "Default")
      (node (ref "U5") (pin "31") (pinfunction "GPIO20_31") (pintype "bidirectional+no_connect"))
    )
    (net (code "54") (name "unconnected-(U5-GPIO21-Pad32)") (class "Default")
      (node (ref "U5") (pin "32") (pinfunction "GPIO21_32") (pintype "bidirectional+no_connect"))
    )
    (net (code "55") (name "unconnected-(U5-GPIO22-Pad34)") (class "Default")
      (node (ref "U5") (pin "34") (pinfunction "GPIO22_34") (pintype "bidirectional+no_connect"))
    )
    (net (code "56") (name "unconnected-(U5-GPIO23-Pad35)") (class "Default")
      (node (ref "U5") (pin "35") (pinfunction "GPIO23_35") (pintype "bidirectional+no_connect"))
    )
    (net (code "57") (name "unconnected-(U5-GPIO24-Pad36)") (class "Default")
      (node (ref "U5") (pin "36") (pinfunction "GPIO24_36") (pintype "bidirectional+no_connect"))
    )
    (net (code "58") (name "unconnected-(U5-GPIO29_ADC3-Pad41)") (class "Default")
      (node (ref "U5") (pin "41") (pinfunction "GPIO29_ADC3_41") (pintype "bidirectional+no_connect"))
    )
    (net (code "59") (name "unconnected-(USB1-EP-Pad1)") (class "Default")
      (node (ref "USB1") (pin "1") (pinfunction "EP_1") (pintype "unspecified+no_connect"))
    )
    (net (code "60") (name "unconnected-(USB1-EP-Pad2)") (class "Default")
      (node (ref "USB1") (pin "2") (pinfunction "EP_2") (pintype "unspecified+no_connect"))
    )
    (net (code "61") (name "unconnected-(USB1-EP-Pad3)") (class "Default")
      (node (ref "USB1") (pin "3") (pinfunction "EP_3") (pintype "unspecified+no_connect"))
    )
    (net (code "62") (name "unconnected-(USB1-EP-Pad4)") (class "Default")
      (node (ref "USB1") (pin "4") (pinfunction "EP_4") (pintype "unspecified+no_connect"))
    )
    (net (code "63") (name "unconnected-(USB1-SUB1-PadA8)") (class "Default")
      (node (ref "USB1") (pin "A8") (pinfunction "SUB1_A8") (pintype "unspecified+no_connect"))
    )
    (net (code "64") (name "unconnected-(USB1-SUB2-PadB8)") (class "Default")
      (node (ref "USB1") (pin "B8") (pinfunction "SUB2_B8") (pintype "unspecified+no_connect"))
    )
  )
)
